# SparkX_EZ_Power_AAA.net
KiCad netlist of a schematic drawn in EAGLE
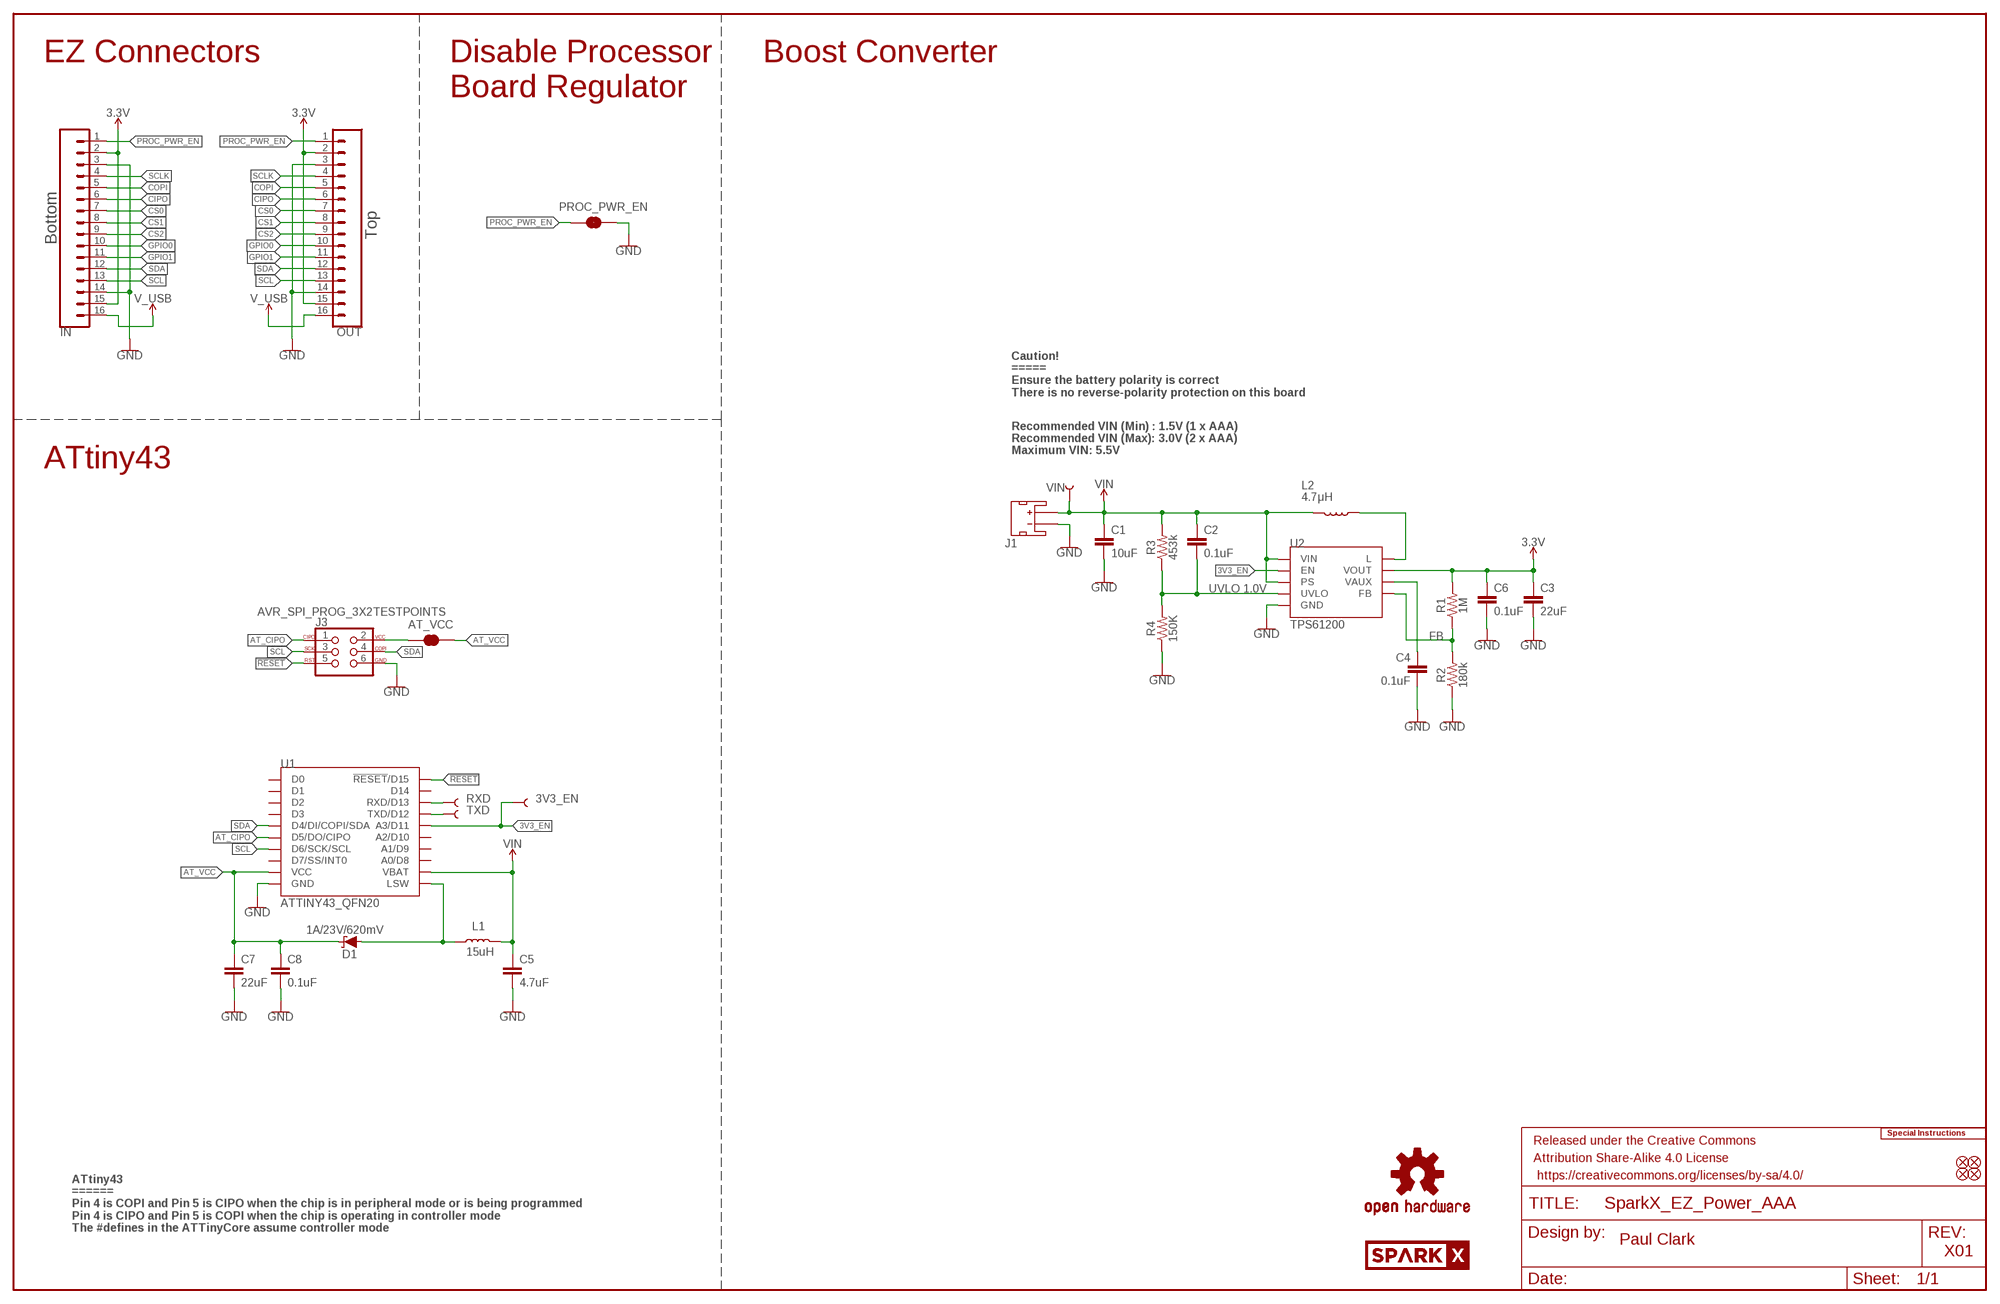
[diagram p0: schematic, sheet 1]

(export (version "E")
  (design (tool "Eeschema 10.0.6"))
  (components
    (comp (ref "3V3_EN")
      (value "TEST-POINT3X4")
      (footprint "eagle-import:PAD.03X.04")
      (libsource (lib "eagle-import") (part "TEST-POINT3X4"))
    )
    (comp (ref "AT_VCC")
      (value "JUMPER-SMT_2_NC_TRACE_SILK")
      (footprint "eagle-import:SMT-JUMPER_2_NC_TRACE_SILK")
      (libsource (lib "eagle-import") (part "JUMPER-SMT_2_NC_TRACE_SILK"))
    )
    (comp (ref "C1")
      (value "10uF")
      (footprint "eagle-import:0402-TIGHT")
      (libsource (lib "eagle-import") (part "10UF-0402T-6.3V-20%"))
    )
    (comp (ref "C2")
      (value "0.1uF")
      (footprint "eagle-import:0402-TIGHT")
      (libsource (lib "eagle-import") (part "0.1UF-0402T-6.3V-10%-X7R"))
    )
    (comp (ref "C3")
      (value "22uF")
      (footprint "eagle-import:0603")
      (libsource (lib "eagle-import") (part "22UF-0603-6.3V-20%"))
    )
    (comp (ref "C4")
      (value "0.1uF")
      (footprint "eagle-import:0402-TIGHT")
      (libsource (lib "eagle-import") (part "0.1UF-0402T-6.3V-10%-X7R"))
    )
    (comp (ref "C5")
      (value "4.7uF")
      (footprint "eagle-import:0402-TIGHT")
      (libsource (lib "eagle-import") (part "4.7UF-0402_TIGHT-6.3V-20%-X5R"))
    )
    (comp (ref "C6")
      (value "0.1uF")
      (footprint "eagle-import:0402-TIGHT")
      (libsource (lib "eagle-import") (part "0.1UF-0402T-6.3V-10%-X7R"))
    )
    (comp (ref "C7")
      (value "22uF")
      (footprint "eagle-import:0603")
      (libsource (lib "eagle-import") (part "22UF-0603-6.3V-20%"))
    )
    (comp (ref "C8")
      (value "0.1uF")
      (footprint "eagle-import:0402-TIGHT")
      (libsource (lib "eagle-import") (part "0.1UF-0402T-6.3V-10%-X7R"))
    )
    (comp (ref "D1")
      (value "1A/23V/620mV")
      (footprint "eagle-import:SOD-323")
      (libsource (lib "eagle-import") (part "DIODE-SCHOTTKY-BAT20J"))
    )
    (comp (ref "FD1")
      (value "FIDUCIALUFIDUCIAL")
      (footprint "eagle-import:FIDUCIAL-MICRO")
      (libsource (lib "eagle-import") (part "FIDUCIALUFIDUCIAL"))
    )
    (comp (ref "FD2")
      (value "FIDUCIALUFIDUCIAL")
      (footprint "eagle-import:FIDUCIAL-MICRO")
      (libsource (lib "eagle-import") (part "FIDUCIALUFIDUCIAL"))
    )
    (comp (ref "FD3")
      (value "FIDUCIALUFIDUCIAL")
      (footprint "eagle-import:FIDUCIAL-MICRO")
      (libsource (lib "eagle-import") (part "FIDUCIALUFIDUCIAL"))
    )
    (comp (ref "FD4")
      (value "FIDUCIALUFIDUCIAL")
      (footprint "eagle-import:FIDUCIAL-MICRO")
      (libsource (lib "eagle-import") (part "FIDUCIALUFIDUCIAL"))
    )
    (comp (ref "FRAME1")
      (value "FRAME-LEDGER")
      (footprint "eagle-import:CREATIVE_COMMONS")
      (libsource (lib "eagle-import") (part "FRAME-LEDGER"))
    )
    (comp (ref "IN")
      (value "CONN_16FPC_16_0.5MM")
      (footprint "eagle-import:FPC_16_0.5MM")
      (libsource (lib "eagle-import") (part "CONN_16FPC_16_0.5MM"))
    )
    (comp (ref "J1")
      (value "JST_2MM_MALE")
      (footprint "eagle-import:JST-2-SMD")
      (libsource (lib "eagle-import") (part "JST_2MM_MALE"))
    )
    (comp (ref "J3")
      (value "AVR_SPI_PROG_3X2TESTPOINTS")
      (footprint "eagle-import:2X3_TEST_POINTS")
      (libsource (lib "eagle-import") (part "AVR_SPI_PROG_3X2TESTPOINTS"))
    )
    (comp (ref "L1")
      (value "15uH")
      (footprint "eagle-import:INDUCTOR_LQH32")
      (libsource (lib "eagle-import") (part "INDUCTOR-LHQ32-15UH"))
    )
    (comp (ref "L2")
      (value "4.7μH")
      (footprint "eagle-import:INDUCTOR_4X4MM")
      (libsource (lib "eagle-import") (part "4.7μH_SHIELDED_INDUCTORNPIS_LS"))
    )
    (comp (ref "LOGO1")
      (value "SPECIAL_INSTRUCTIONS-ORDERING")
      (footprint "eagle-import:ORDERING_INSTRUCTIONS")
      (libsource (lib "eagle-import") (part "SPECIAL_INSTRUCTIONS-ORDERING"))
    )
    (comp (ref "LOGO2")
      (value "OSHW-LOGOMINI")
      (footprint "eagle-import:OSHW-LOGO-MINI")
      (libsource (lib "eagle-import") (part "OSHW-LOGOMINI"))
    )
    (comp (ref "LOGO3")
      (value "OSHW-LOGOMINI")
      (footprint "eagle-import:OSHW-LOGO-MINI")
      (libsource (lib "eagle-import") (part "OSHW-LOGOMINI"))
    )
    (comp (ref "OUT")
      (value "CONN_16FPC_16_0.5MM")
      (footprint "eagle-import:FPC_16_0.5MM")
      (libsource (lib "eagle-import") (part "CONN_16FPC_16_0.5MM"))
    )
    (comp (ref "PROC_PWR_EN")
      (value "JUMPER-SMT_2_NC_TRACE_SILK")
      (footprint "eagle-import:SMT-JUMPER_2_NC_TRACE_SILK")
      (libsource (lib "eagle-import") (part "JUMPER-SMT_2_NC_TRACE_SILK"))
    )
    (comp (ref "R1")
      (value "1M")
      (footprint "eagle-import:0402-TIGHT")
      (libsource (lib "eagle-import") (part "1MOHM-0402T-1/16W-5%"))
    )
    (comp (ref "R2")
      (value "180k")
      (footprint "eagle-import:0402-TIGHT")
      (libsource (lib "eagle-import") (part "180KOHM-0402T-1/16W-1%"))
    )
    (comp (ref "R3")
      (value "453k")
      (footprint "eagle-import:0402-TIGHT")
      (libsource (lib "eagle-import") (part "453KOHM-0402T-1/16W-1%"))
    )
    (comp (ref "R4")
      (value "150K")
      (footprint "eagle-import:0402-TIGHT")
      (libsource (lib "eagle-import") (part "150KOHM-0402T-1/16W-1%"))
    )
    (comp (ref "RXD")
      (value "TEST-POINT3X4")
      (footprint "eagle-import:PAD.03X.04")
      (libsource (lib "eagle-import") (part "TEST-POINT3X4"))
    )
    (comp (ref "TXD")
      (value "TEST-POINT3X4")
      (footprint "eagle-import:PAD.03X.04")
      (libsource (lib "eagle-import") (part "TEST-POINT3X4"))
    )
    (comp (ref "U$1")
      (value "SPARKX-LOGO3")
      (footprint "eagle-import:SPARKX-SMALL")
      (libsource (lib "eagle-import") (part "SPARKX-LOGO3"))
    )
    (comp (ref "U1")
      (value "ATTINY43_QFN20")
      (footprint "eagle-import:QFN20_20M1")
      (fields (field (name "DIGIKEY_PART") "ATTINY43U-MU-ND") (field (name "MANU_PART") "ATtiny43U-MU"))
      (libsource (lib "eagle-import") (part "ATTINY43_QFN20"))
    )
    (comp (ref "U2")
      (value "TPS61200")
      (footprint "eagle-import:QFN-10_PAD")
      (libsource (lib "eagle-import") (part "TPS61200_MINIMAL"))
    )
    (comp (ref "VIN")
      (value "TEST-POINT3X4")
      (footprint "eagle-import:PAD.03X.04")
      (libsource (lib "eagle-import") (part "TEST-POINT3X4"))
    )
  )
  (nets
    (net (code "1") (name "/FB") (class "Default")
      (node (ref "R1") (pin "1") (pinfunction "1_1") (pintype "passive"))
      (node (ref "R2") (pin "2") (pinfunction "2_2") (pintype "passive"))
      (node (ref "U2") (pin "10") (pinfunction "FB_10") (pintype "passive"))
    )
    (net (code "2") (name "/~{RESET}") (class "Default")
      (node (ref "J3") (pin "5") (pinfunction "5_5") (pintype "passive"))
      (node (ref "U1") (pin "18") (pinfunction "~{RESET}/D15_18") (pintype "bidirectional"))
    )
    (net (code "3") (name "3.3V") (class "Default")
      (node (ref "C3") (pin "1") (pinfunction "1_1") (pintype "passive"))
      (node (ref "C6") (pin "1") (pinfunction "1_1") (pintype "passive"))
      (node (ref "IN") (pin "15") (pinfunction "15_15") (pintype "passive"))
      (node (ref "IN") (pin "2") (pinfunction "2_2") (pintype "passive"))
      (node (ref "OUT") (pin "15") (pinfunction "15_15") (pintype "passive"))
      (node (ref "OUT") (pin "2") (pinfunction "2_2") (pintype "passive"))
      (node (ref "R1") (pin "2") (pinfunction "2_2") (pintype "passive"))
      (node (ref "U2") (pin "2") (pinfunction "VOUT_2") (pintype "power_in"))
    )
    (net (code "4") (name "3V3_EN") (class "Default")
      (node (ref "3V3_EN") (pin "1") (pinfunction "1_1") (pintype "bidirectional"))
      (node (ref "U1") (pin "14") (pinfunction "A3/D11_14") (pintype "bidirectional"))
      (node (ref "U2") (pin "6") (pinfunction "EN_6") (pintype "input"))
    )
    (net (code "5") (name "AT_CIPO") (class "Default")
      (node (ref "J3") (pin "1") (pinfunction "1_1") (pintype "passive"))
      (node (ref "U1") (pin "4") (pinfunction "D5/DO/CIPO_4") (pintype "bidirectional"))
    )
    (net (code "6") (name "AT_VCC") (class "Default")
      (node (ref "AT_VCC") (pin "2") (pinfunction "2_2") (pintype "passive"))
      (node (ref "C7") (pin "1") (pinfunction "1_1") (pintype "passive"))
      (node (ref "C8") (pin "1") (pinfunction "1_1") (pintype "passive"))
      (node (ref "D1") (pin "C") (pinfunction "C_C") (pintype "passive"))
      (node (ref "U1") (pin "7") (pinfunction "VCC_7") (pintype "power_in"))
    )
    (net (code "7") (name "CIPO") (class "Default")
      (node (ref "IN") (pin "6") (pinfunction "6_6") (pintype "passive"))
      (node (ref "OUT") (pin "6") (pinfunction "6_6") (pintype "passive"))
    )
    (net (code "8") (name "COPI") (class "Default")
      (node (ref "IN") (pin "5") (pinfunction "5_5") (pintype "passive"))
      (node (ref "OUT") (pin "5") (pinfunction "5_5") (pintype "passive"))
    )
    (net (code "9") (name "CS0") (class "Default")
      (node (ref "IN") (pin "7") (pinfunction "7_7") (pintype "passive"))
      (node (ref "OUT") (pin "7") (pinfunction "7_7") (pintype "passive"))
    )
    (net (code "10") (name "CS1") (class "Default")
      (node (ref "IN") (pin "8") (pinfunction "8_8") (pintype "passive"))
      (node (ref "OUT") (pin "8") (pinfunction "8_8") (pintype "passive"))
    )
    (net (code "11") (name "CS2") (class "Default")
      (node (ref "IN") (pin "9") (pinfunction "9_9") (pintype "passive"))
      (node (ref "OUT") (pin "9") (pinfunction "9_9") (pintype "passive"))
    )
    (net (code "12") (name "GND") (class "Default")
      (node (ref "C1") (pin "2") (pinfunction "2_2") (pintype "passive"))
      (node (ref "C3") (pin "2") (pinfunction "2_2") (pintype "passive"))
      (node (ref "C4") (pin "2") (pinfunction "2_2") (pintype "passive"))
      (node (ref "C5") (pin "2") (pinfunction "2_2") (pintype "passive"))
      (node (ref "C6") (pin "2") (pinfunction "2_2") (pintype "passive"))
      (node (ref "C7") (pin "2") (pinfunction "2_2") (pintype "passive"))
      (node (ref "C8") (pin "2") (pinfunction "2_2") (pintype "passive"))
      (node (ref "IN") (pin "14") (pinfunction "14_14") (pintype "passive"))
      (node (ref "IN") (pin "3") (pinfunction "3_3") (pintype "passive"))
      (node (ref "J1") (pin "1") (pinfunction "-_1") (pintype "bidirectional"))
      (node (ref "J3") (pin "6") (pinfunction "6_6") (pintype "passive"))
      (node (ref "OUT") (pin "14") (pinfunction "14_14") (pintype "passive"))
      (node (ref "OUT") (pin "3") (pinfunction "3_3") (pintype "passive"))
      (node (ref "PROC_PWR_EN") (pin "2") (pinfunction "2_2") (pintype "passive"))
      (node (ref "R2") (pin "1") (pinfunction "1_1") (pintype "passive"))
      (node (ref "R4") (pin "1") (pinfunction "1_1") (pintype "passive"))
      (node (ref "U1") (pin "8") (pinfunction "GND_8") (pintype "power_in"))
      (node (ref "U1") (pin "PAD") (pinfunction "GND_PAD") (pintype "power_in"))
      (node (ref "U2") (pin "11") (pinfunction "GND_11") (pintype "power_in"))
      (node (ref "U2") (pin "12") (pinfunction "GND_12") (pintype "power_in"))
      (node (ref "U2") (pin "13") (pinfunction "GND_13") (pintype "power_in"))
      (node (ref "U2") (pin "14") (pinfunction "GND_14") (pintype "power_in"))
      (node (ref "U2") (pin "15") (pinfunction "GND_15") (pintype "power_in"))
      (node (ref "U2") (pin "4") (pinfunction "GND_4") (pintype "power_in"))
      (node (ref "U2") (pin "9") (pinfunction "GND_9") (pintype "power_in"))
    )
    (net (code "13") (name "GPIO0") (class "Default")
      (node (ref "IN") (pin "10") (pinfunction "10_10") (pintype "passive"))
      (node (ref "OUT") (pin "10") (pinfunction "10_10") (pintype "passive"))
    )
    (net (code "14") (name "GPIO1") (class "Default")
      (node (ref "IN") (pin "11") (pinfunction "11_11") (pintype "passive"))
      (node (ref "OUT") (pin "11") (pinfunction "11_11") (pintype "passive"))
    )
    (net (code "15") (name "Net-(AT_VCC-Pad1)") (class "Default")
      (node (ref "AT_VCC") (pin "1") (pinfunction "1_1") (pintype "passive"))
      (node (ref "J3") (pin "2") (pinfunction "2_2") (pintype "passive"))
    )
    (net (code "16") (name "Net-(L1-1)") (class "Default")
      (node (ref "D1") (pin "A") (pinfunction "A_A") (pintype "passive"))
      (node (ref "L1") (pin "P$1") (pinfunction "1_P$1") (pintype "passive"))
      (node (ref "U1") (pin "9") (pinfunction "LSW_9") (pintype "power_in"))
    )
    (net (code "17") (name "Net-(L2-1)") (class "Default")
      (node (ref "L2") (pin "P$1") (pinfunction "1_P$1") (pintype "passive"))
      (node (ref "U2") (pin "3") (pinfunction "L_3") (pintype "passive"))
    )
    (net (code "18") (name "Net-(U1-RXD{slash}D13)") (class "Default")
      (node (ref "RXD") (pin "1") (pinfunction "1_1") (pintype "bidirectional"))
      (node (ref "U1") (pin "16") (pinfunction "RXD/D13_16") (pintype "bidirectional"))
    )
    (net (code "19") (name "Net-(U1-TXD{slash}D12)") (class "Default")
      (node (ref "TXD") (pin "1") (pinfunction "1_1") (pintype "bidirectional"))
      (node (ref "U1") (pin "15") (pinfunction "TXD/D12_15") (pintype "bidirectional"))
    )
    (net (code "20") (name "Net-(U2-UVLO)") (class "Default")
      (node (ref "C2") (pin "2") (pinfunction "2_2") (pintype "passive"))
      (node (ref "R3") (pin "1") (pinfunction "1_1") (pintype "passive"))
      (node (ref "R4") (pin "2") (pinfunction "2_2") (pintype "passive"))
      (node (ref "U2") (pin "7") (pinfunction "UVLO_7") (pintype "input"))
    )
    (net (code "21") (name "Net-(U2-VAUX)") (class "Default")
      (node (ref "C4") (pin "1") (pinfunction "1_1") (pintype "passive"))
      (node (ref "U2") (pin "1") (pinfunction "VAUX_1") (pintype "passive"))
    )
    (net (code "22") (name "PROC_PWR_EN") (class "Default")
      (node (ref "IN") (pin "1") (pinfunction "1_1") (pintype "passive"))
      (node (ref "OUT") (pin "1") (pinfunction "1_1") (pintype "passive"))
      (node (ref "PROC_PWR_EN") (pin "1") (pinfunction "1_1") (pintype "passive"))
    )
    (net (code "23") (name "SCL") (class "Default")
      (node (ref "IN") (pin "13") (pinfunction "13_13") (pintype "passive"))
      (node (ref "J3") (pin "3") (pinfunction "3_3") (pintype "passive"))
      (node (ref "OUT") (pin "13") (pinfunction "13_13") (pintype "passive"))
      (node (ref "U1") (pin "5") (pinfunction "D6/SCK/SCL_5") (pintype "bidirectional"))
    )
    (net (code "24") (name "SCLK") (class "Default")
      (node (ref "IN") (pin "4") (pinfunction "4_4") (pintype "passive"))
      (node (ref "OUT") (pin "4") (pinfunction "4_4") (pintype "passive"))
    )
    (net (code "25") (name "SDA") (class "Default")
      (node (ref "IN") (pin "12") (pinfunction "12_12") (pintype "passive"))
      (node (ref "J3") (pin "4") (pinfunction "4_4") (pintype "passive"))
      (node (ref "OUT") (pin "12") (pinfunction "12_12") (pintype "passive"))
      (node (ref "U1") (pin "3") (pinfunction "D4/DI/COPI/SDA_3") (pintype "bidirectional"))
    )
    (net (code "26") (name "VIN") (class "Default")
      (node (ref "C1") (pin "1") (pinfunction "1_1") (pintype "passive"))
      (node (ref "C2") (pin "1") (pinfunction "1_1") (pintype "passive"))
      (node (ref "C5") (pin "1") (pinfunction "1_1") (pintype "passive"))
      (node (ref "J1") (pin "2") (pinfunction "+_2") (pintype "bidirectional"))
      (node (ref "L1") (pin "P$2") (pinfunction "2_P$2") (pintype "passive"))
      (node (ref "L2") (pin "P$2") (pinfunction "2_P$2") (pintype "passive"))
      (node (ref "R3") (pin "2") (pinfunction "2_2") (pintype "passive"))
      (node (ref "U1") (pin "10") (pinfunction "VBAT_10") (pintype "power_in"))
      (node (ref "U2") (pin "5") (pinfunction "VIN_5") (pintype "power_in"))
      (node (ref "U2") (pin "8") (pinfunction "PS_8") (pintype "input"))
      (node (ref "VIN") (pin "1") (pinfunction "1_1") (pintype "bidirectional"))
    )
    (net (code "27") (name "V_USB") (class "Default")
      (node (ref "IN") (pin "16") (pinfunction "16_16") (pintype "passive"))
      (node (ref "OUT") (pin "16") (pinfunction "16_16") (pintype "passive"))
    )
    (net (code "28") (name "unconnected-(J1-PAD1-PadNC1)") (class "Default")
      (node (ref "J1") (pin "NC1") (pinfunction "PAD1_NC1") (pintype "bidirectional"))
    )
    (net (code "29") (name "unconnected-(J1-PAD2-PadNC2)") (class "Default")
      (node (ref "J1") (pin "NC2") (pinfunction "PAD2_NC2") (pintype "bidirectional"))
    )
    (net (code "30") (name "unconnected-(U1-A0{slash}D8-Pad11)") (class "Default")
      (node (ref "U1") (pin "11") (pinfunction "A0/D8_11") (pintype "bidirectional"))
    )
    (net (code "31") (name "unconnected-(U1-A1{slash}D9-Pad12)") (class "Default")
      (node (ref "U1") (pin "12") (pinfunction "A1/D9_12") (pintype "bidirectional"))
    )
    (net (code "32") (name "unconnected-(U1-A2{slash}D10-Pad13)") (class "Default")
      (node (ref "U1") (pin "13") (pinfunction "A2/D10_13") (pintype "bidirectional"))
    )
    (net (code "33") (name "unconnected-(U1-D0-Pad19)") (class "Default")
      (node (ref "U1") (pin "19") (pinfunction "D0_19") (pintype "bidirectional"))
    )
    (net (code "34") (name "unconnected-(U1-D1-Pad20)") (class "Default")
      (node (ref "U1") (pin "20") (pinfunction "D1_20") (pintype "bidirectional"))
    )
    (net (code "35") (name "unconnected-(U1-D2-Pad1)") (class "Default")
      (node (ref "U1") (pin "1") (pinfunction "D2_1") (pintype "bidirectional"))
    )
    (net (code "36") (name "unconnected-(U1-D3-Pad2)") (class "Default")
      (node (ref "U1") (pin "2") (pinfunction "D3_2") (pintype "bidirectional"))
    )
    (net (code "37") (name "unconnected-(U1-D7{slash}SS{slash}INT0-Pad6)") (class "Default")
      (node (ref "U1") (pin "6") (pinfunction "D7/SS/INT0_6") (pintype "bidirectional"))
    )
    (net (code "38") (name "unconnected-(U1-D14-Pad17)") (class "Default")
      (node (ref "U1") (pin "17") (pinfunction "D14_17") (pintype "bidirectional"))
    )
  )
)
